# 3_ADSTM32-Peripherals.net
KiCad netlist of a schematic drawn in Altium Designer
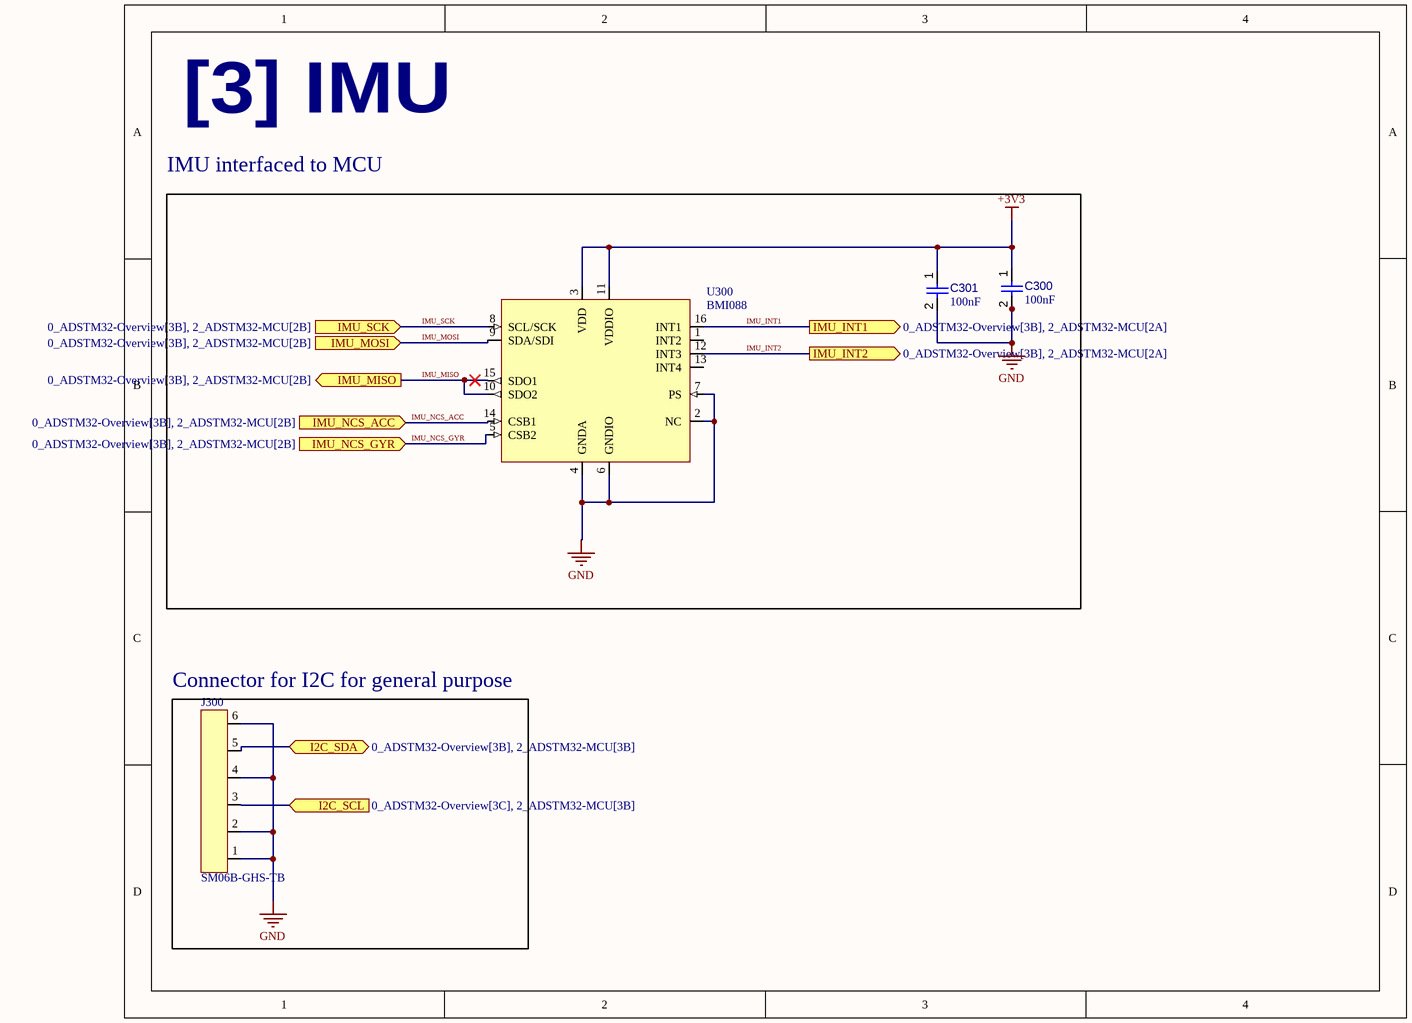
[diagram p0: 3_ADSTM32-Peripherals.SchDoc]

(export (version "E")
  (design (tool "Eeschema 10.0.6"))
  (components
    (comp (ref "C300")
      (value "100nF")
      (footprint "CAPC1608X90X40NL10T20")
      (description "Chip Capacitor, 100 nF, +/- 10%, 50 V, 0603 (1608 Metric)")
      (fields (field (name "TOLERANCE") "10%") (field (name "Comment") "Capacitor 100 nF +/-10% 50 V 0603"))
      (libsource (lib "Technische Universität Darmstadt -  Institut für Stromrichtertechnik und Antriebsregelung") (part "CAP-NP-2"))
    )
    (comp (ref "C301")
      (value "100nF")
      (footprint "CAPC1608X90X40NL10T20")
      (description "Chip Capacitor, 100 nF, +/- 10%, 50 V, 0603 (1608 Metric)")
      (fields (field (name "TOLERANCE") "10%") (field (name "Comment") "Capacitor 100 nF +/-10% 50 V 0603"))
      (libsource (lib "Technische Universität Darmstadt -  Institut für Stromrichtertechnik und Antriebsregelung") (part "CAP-NP-2"))
    )
    (comp (ref "J300")
      (value "SM06B-GHS-TB")
      (footprint "SM06B-GHS-TB")
      (description "Header Connector 6 Position 1.25MM Pitch SMD Horizontal JST GH")
      (fields (field (name "MANUFACTURER") "JST"))
      (libsource (lib "Schematic-Lib-PhilsLab") (part "SM06B-GHS-TB"))
    )
    (comp (ref "U300")
      (value "BMI088")
      (footprint "BMI088")
      (description "Inertial Measurement Unit IMU 6-Axis LGA")
      (fields (field (name "MANUFACTURER") "Bosch"))
      (libsource (lib "Schematic-Lib-PhilsLab") (part "BMI088"))
    )
  )
  (nets
    (net (code "1") (name "+3V3") (class "Default")
      (node (ref "C300") (pin "1") (pinfunction "1_1") (pintype "passive"))
      (node (ref "C301") (pin "1") (pinfunction "1_1") (pintype "passive"))
      (node (ref "U300") (pin "11") (pinfunction "VDDIO_11") (pintype "power_in"))
      (node (ref "U300") (pin "3") (pinfunction "VDD_3") (pintype "power_in"))
    )
    (net (code "2") (name "/I2C_SCL") (class "Default")
      (node (ref "J300") (pin "3") (pinfunction "3_3") (pintype "passive"))
    )
    (net (code "3") (name "/I2C_SDA") (class "Default")
      (node (ref "J300") (pin "5") (pinfunction "5_5") (pintype "passive"))
    )
    (net (code "4") (name "/IMU_INT1") (class "Default")
      (node (ref "U300") (pin "16") (pinfunction "INT1_16") (pintype "bidirectional"))
    )
    (net (code "5") (name "/IMU_INT2") (class "Default")
      (node (ref "U300") (pin "12") (pinfunction "INT3_12") (pintype "bidirectional"))
    )
    (net (code "6") (name "/IMU_MISO") (class "Default")
      (node (ref "U300") (pin "10") (pinfunction "SDO2_10") (pintype "output"))
      (node (ref "U300") (pin "15") (pinfunction "SDO1_15") (pintype "output"))
    )
    (net (code "7") (name "/IMU_MOSI") (class "Default")
      (node (ref "U300") (pin "9") (pinfunction "SDA/SDI_9") (pintype "bidirectional"))
    )
    (net (code "8") (name "/IMU_NCS_ACC") (class "Default")
      (node (ref "U300") (pin "14") (pinfunction "CSB1_14") (pintype "input"))
    )
    (net (code "9") (name "/IMU_NCS_GYR") (class "Default")
      (node (ref "U300") (pin "5") (pinfunction "CSB2_5") (pintype "input"))
    )
    (net (code "10") (name "/IMU_SCK") (class "Default")
      (node (ref "U300") (pin "8") (pinfunction "SCL/SCK_8") (pintype "input"))
    )
    (net (code "11") (name "GND") (class "Default")
      (node (ref "C300") (pin "2") (pinfunction "2_2") (pintype "passive"))
      (node (ref "C301") (pin "2") (pinfunction "2_2") (pintype "passive"))
      (node (ref "J300") (pin "1") (pinfunction "1_1") (pintype "passive"))
      (node (ref "J300") (pin "2") (pinfunction "2_2") (pintype "passive"))
      (node (ref "J300") (pin "4") (pinfunction "4_4") (pintype "passive"))
      (node (ref "J300") (pin "6") (pinfunction "6_6") (pintype "passive"))
      (node (ref "U300") (pin "2") (pinfunction "NC_2") (pintype "passive"))
      (node (ref "U300") (pin "4") (pinfunction "GNDA_4") (pintype "power_in"))
      (node (ref "U300") (pin "6") (pinfunction "GNDIO_6") (pintype "power_in"))
      (node (ref "U300") (pin "7") (pinfunction "PS_7") (pintype "input"))
    )
    (net (code "12") (name "unconnected-(U300-INT2-Pad1)") (class "Default")
      (node (ref "U300") (pin "1") (pinfunction "INT2_1") (pintype "bidirectional"))
    )
    (net (code "13") (name "unconnected-(U300-INT4-Pad13)") (class "Default")
      (node (ref "U300") (pin "13") (pinfunction "INT4_13") (pintype "bidirectional"))
    )
  )
)
